# ClipBoard.net
KiCad netlist of a schematic drawn in EAGLE
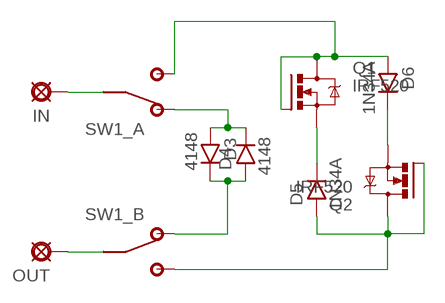
[diagram p0: schematic, sheet 1]

(export (version "E")
  (design (tool "Eeschema 10.0.6"))
  (components
    (comp (ref "D3")
      (value "4148")
      (footprint "eagle-import:DO35-3")
      (libsource (lib "eagle-import") (part "1N4148-3"))
    )
    (comp (ref "D4")
      (value "4148")
      (footprint "eagle-import:DO35-3")
      (libsource (lib "eagle-import") (part "1N4148-3"))
    )
    (comp (ref "D5")
      (value "1N34A")
      (footprint "eagle-import:DO07")
      (libsource (lib "eagle-import") (part "DO07"))
    )
    (comp (ref "D6")
      (value "1N34A")
      (footprint "eagle-import:DO07")
      (libsource (lib "eagle-import") (part "DO07"))
    )
    (comp (ref "IN")
      (value "CLIPIN")
      (footprint "eagle-import:SQUARE")
      (libsource (lib "eagle-import") (part "PAD"))
    )
    (comp (ref "OUT")
      (value "CLIPOUT")
      (footprint "eagle-import:SQUARE")
      (libsource (lib "eagle-import") (part "PAD"))
    )
    (comp (ref "Q1")
      (value "IRF520")
      (footprint "eagle-import:TO220BV")
      (libsource (lib "eagle-import") (part "IRF520"))
    )
    (comp (ref "Q2")
      (value "IRF520")
      (footprint "eagle-import:TO220BV")
      (libsource (lib "eagle-import") (part "IRF520"))
    )
    (comp (ref "SW1")
      (value "DPDT")
      (footprint "eagle-import:DPDT_PCB")
      (libsource (lib "eagle-import") (part "DPDTDPDT_2"))
    )
  )
  (nets
    (net (code "1") (name "Net-(D5-PadC)") (class "Default")
      (node (ref "D5") (pin "C") (pinfunction "C_C") (pintype "passive"))
      (node (ref "Q1") (pin "S") (pinfunction "S_S") (pintype "passive"))
    )
    (net (code "2") (name "Net-(D6-PadC)") (class "Default")
      (node (ref "D6") (pin "C") (pinfunction "C_C") (pintype "passive"))
      (node (ref "Q2") (pin "S") (pinfunction "S_S") (pintype "passive"))
    )
    (net (code "3") (name "Net-(IN-PAD)") (class "Default")
      (node (ref "IN") (pin "1") (pinfunction "PAD_1") (pintype "passive"))
      (node (ref "SW1") (pin "A1") (pinfunction "2_A1") (pintype "passive"))
    )
    (net (code "4") (name "Net-(OUT-PAD)") (class "Default")
      (node (ref "OUT") (pin "1") (pinfunction "PAD_1") (pintype "passive"))
      (node (ref "SW1") (pin "B1") (pinfunction "2_B1") (pintype "passive"))
    )
    (net (code "5") (name "Net-(SW1A-1)") (class "Default")
      (node (ref "D3") (pin "A") (pinfunction "A_A") (pintype "passive"))
      (node (ref "D4") (pin "C") (pinfunction "C_C") (pintype "passive"))
      (node (ref "SW1") (pin "A2") (pinfunction "1_A2") (pintype "passive"))
    )
    (net (code "6") (name "Net-(SW1A-3)") (class "Default")
      (node (ref "D6") (pin "A") (pinfunction "A_A") (pintype "passive"))
      (node (ref "Q1") (pin "D") (pinfunction "D_D") (pintype "passive"))
      (node (ref "Q1") (pin "G") (pinfunction "G_G") (pintype "passive"))
      (node (ref "SW1") (pin "A3") (pinfunction "3_A3") (pintype "passive"))
    )
    (net (code "7") (name "Net-(SW1B-1)") (class "Default")
      (node (ref "D3") (pin "C") (pinfunction "C_C") (pintype "passive"))
      (node (ref "D4") (pin "A") (pinfunction "A_A") (pintype "passive"))
      (node (ref "SW1") (pin "B2") (pinfunction "1_B2") (pintype "passive"))
    )
    (net (code "8") (name "Net-(SW1B-3)") (class "Default")
      (node (ref "D5") (pin "A") (pinfunction "A_A") (pintype "passive"))
      (node (ref "Q2") (pin "D") (pinfunction "D_D") (pintype "passive"))
      (node (ref "Q2") (pin "G") (pinfunction "G_G") (pintype "passive"))
      (node (ref "SW1") (pin "B3") (pinfunction "3_B3") (pintype "passive"))
    )
  )
)
